# 16ChFNIRS.net
KiCad netlist of a schematic drawn in EAGLE
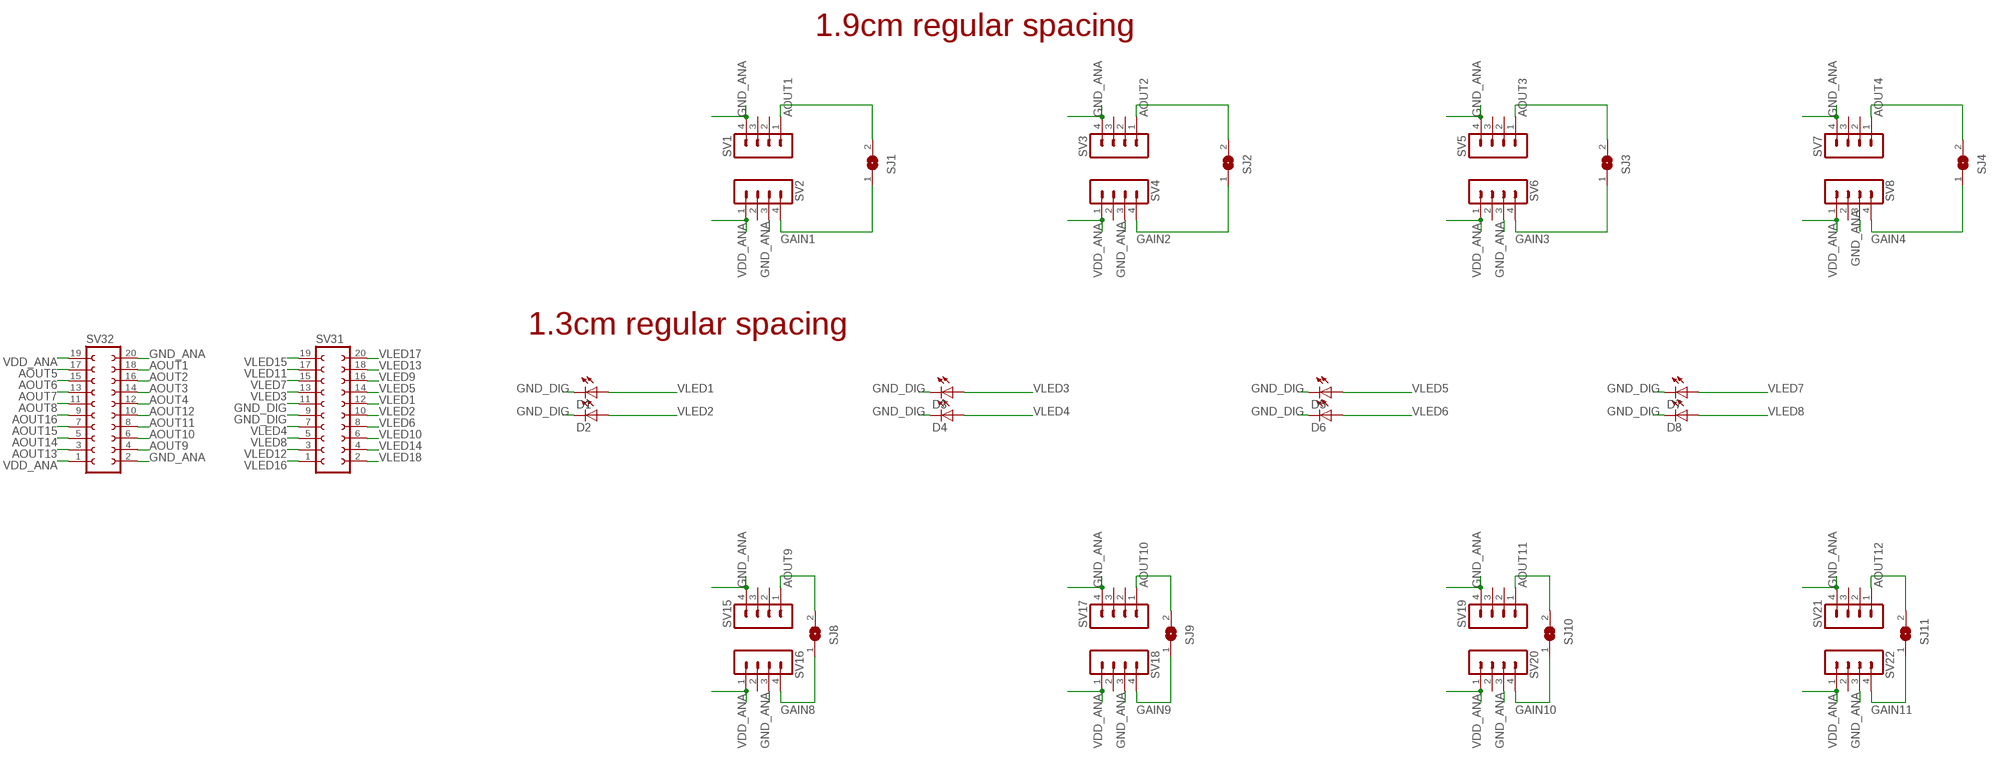
[diagram p0: schematic, sheet 1, part 1 of 2]
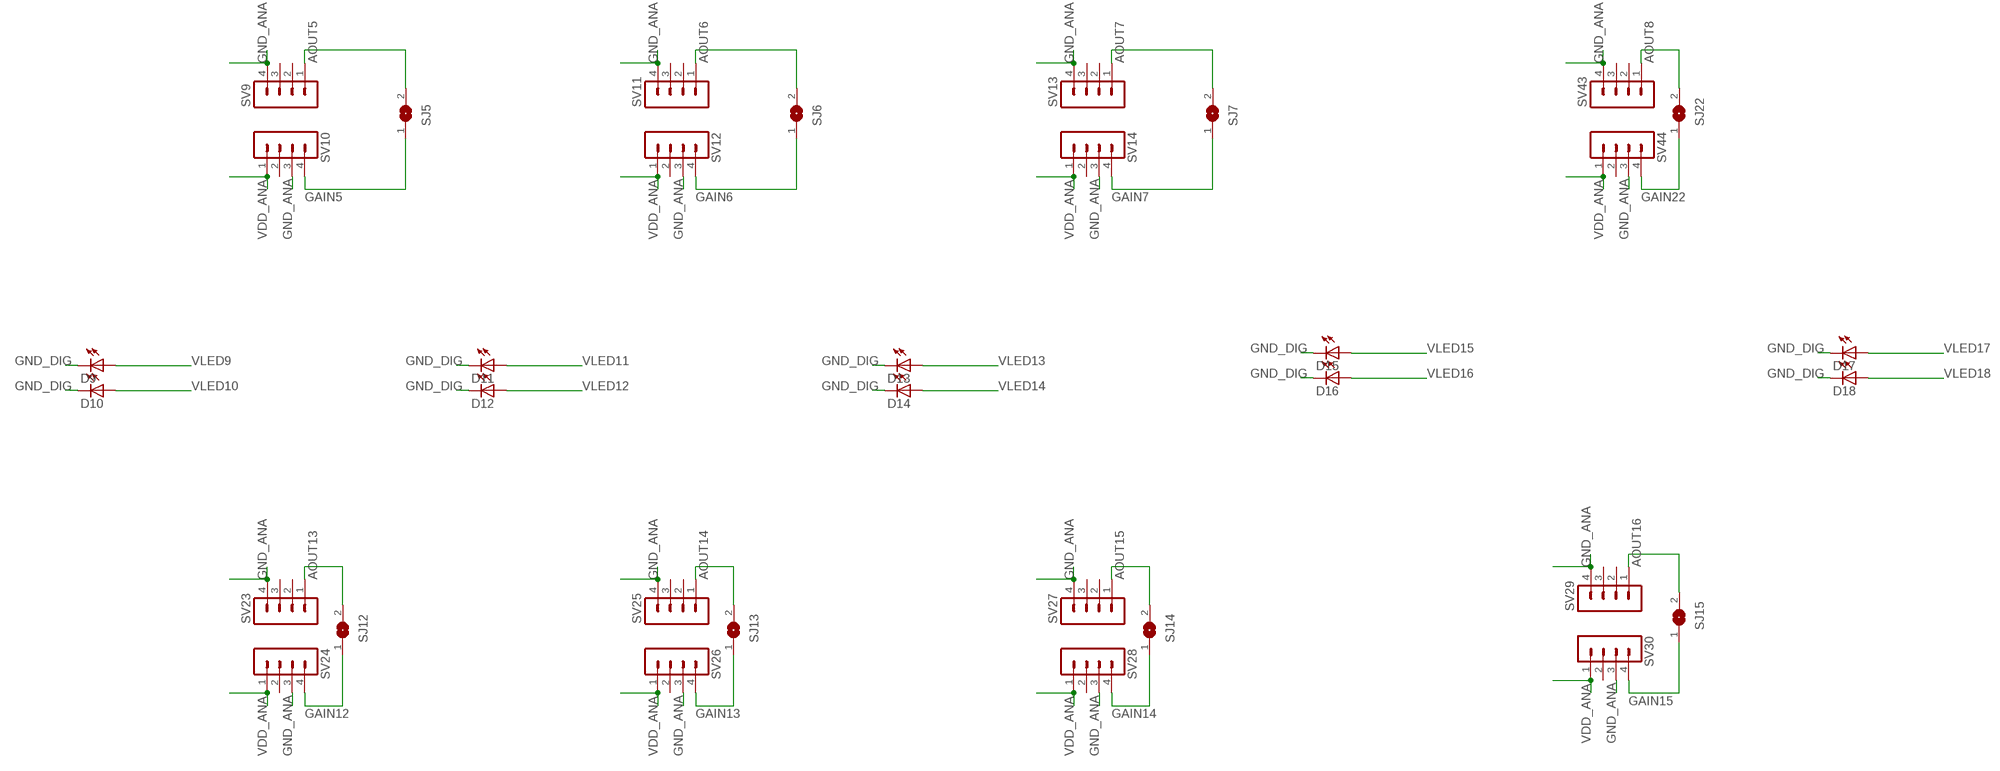
[diagram p1: schematic, sheet 1, part 2 of 2]

(export (version "E")
  (design (tool "Eeschema 10.0.6"))
  (components
    (comp (ref "D1")
      (value "LED1206")
      (footprint "eagle-import:LED-1206")
      (libsource (lib "eagle-import") (part "LED1206"))
    )
    (comp (ref "D2")
      (value "LED1206")
      (footprint "eagle-import:LED-1206")
      (libsource (lib "eagle-import") (part "LED1206"))
    )
    (comp (ref "D3")
      (value "LED1206")
      (footprint "eagle-import:LED-1206")
      (libsource (lib "eagle-import") (part "LED1206"))
    )
    (comp (ref "D4")
      (value "LED1206")
      (footprint "eagle-import:LED-1206")
      (libsource (lib "eagle-import") (part "LED1206"))
    )
    (comp (ref "D5")
      (value "LED1206")
      (footprint "eagle-import:LED-1206")
      (libsource (lib "eagle-import") (part "LED1206"))
    )
    (comp (ref "D6")
      (value "LED1206")
      (footprint "eagle-import:LED-1206")
      (libsource (lib "eagle-import") (part "LED1206"))
    )
    (comp (ref "D7")
      (value "LED1206")
      (footprint "eagle-import:LED-1206")
      (libsource (lib "eagle-import") (part "LED1206"))
    )
    (comp (ref "D8")
      (value "LED1206")
      (footprint "eagle-import:LED-1206")
      (libsource (lib "eagle-import") (part "LED1206"))
    )
    (comp (ref "D9")
      (value "LED1206")
      (footprint "eagle-import:LED-1206")
      (libsource (lib "eagle-import") (part "LED1206"))
    )
    (comp (ref "D10")
      (value "LED1206")
      (footprint "eagle-import:LED-1206")
      (libsource (lib "eagle-import") (part "LED1206"))
    )
    (comp (ref "D11")
      (value "LED1206")
      (footprint "eagle-import:LED-1206")
      (libsource (lib "eagle-import") (part "LED1206"))
    )
    (comp (ref "D12")
      (value "LED1206")
      (footprint "eagle-import:LED-1206")
      (libsource (lib "eagle-import") (part "LED1206"))
    )
    (comp (ref "D13")
      (value "LED1206")
      (footprint "eagle-import:LED-1206")
      (libsource (lib "eagle-import") (part "LED1206"))
    )
    (comp (ref "D14")
      (value "LED1206")
      (footprint "eagle-import:LED-1206")
      (libsource (lib "eagle-import") (part "LED1206"))
    )
    (comp (ref "D15")
      (value "LED1206")
      (footprint "eagle-import:LED-1206")
      (libsource (lib "eagle-import") (part "LED1206"))
    )
    (comp (ref "D16")
      (value "LED1206")
      (footprint "eagle-import:LED-1206")
      (libsource (lib "eagle-import") (part "LED1206"))
    )
    (comp (ref "D17")
      (value "LED1206")
      (footprint "eagle-import:LED-1206")
      (libsource (lib "eagle-import") (part "LED1206"))
    )
    (comp (ref "D18")
      (value "LED1206")
      (footprint "eagle-import:LED-1206")
      (libsource (lib "eagle-import") (part "LED1206"))
    )
    (comp (ref "SJ1") (value "SJ") (footprint "eagle-import:SJ") (libsource (lib "eagle-import") (part "SJ")))
    (comp (ref "SJ2") (value "SJ") (footprint "eagle-import:SJ") (libsource (lib "eagle-import") (part "SJ")))
    (comp (ref "SJ3") (value "SJ") (footprint "eagle-import:SJ") (libsource (lib "eagle-import") (part "SJ")))
    (comp (ref "SJ4") (value "SJ") (footprint "eagle-import:SJ") (libsource (lib "eagle-import") (part "SJ")))
    (comp (ref "SJ5") (value "SJ") (footprint "eagle-import:SJ") (libsource (lib "eagle-import") (part "SJ")))
    (comp (ref "SJ6") (value "SJ") (footprint "eagle-import:SJ") (libsource (lib "eagle-import") (part "SJ")))
    (comp (ref "SJ7") (value "SJ") (footprint "eagle-import:SJ") (libsource (lib "eagle-import") (part "SJ")))
    (comp (ref "SJ8") (value "SJ") (footprint "eagle-import:SJ") (libsource (lib "eagle-import") (part "SJ")))
    (comp (ref "SJ9") (value "SJ") (footprint "eagle-import:SJ") (libsource (lib "eagle-import") (part "SJ")))
    (comp (ref "SJ10")
      (value "SJ")
      (footprint "eagle-import:SJ")
      (libsource (lib "eagle-import") (part "SJ"))
    )
    (comp (ref "SJ11")
      (value "SJ")
      (footprint "eagle-import:SJ")
      (libsource (lib "eagle-import") (part "SJ"))
    )
    (comp (ref "SJ12")
      (value "SJ")
      (footprint "eagle-import:SJ")
      (libsource (lib "eagle-import") (part "SJ"))
    )
    (comp (ref "SJ13")
      (value "SJ")
      (footprint "eagle-import:SJ")
      (libsource (lib "eagle-import") (part "SJ"))
    )
    (comp (ref "SJ14")
      (value "SJ")
      (footprint "eagle-import:SJ")
      (libsource (lib "eagle-import") (part "SJ"))
    )
    (comp (ref "SJ15")
      (value "SJ")
      (footprint "eagle-import:SJ")
      (libsource (lib "eagle-import") (part "SJ"))
    )
    (comp (ref "SJ22")
      (value "SJ")
      (footprint "eagle-import:SJ")
      (libsource (lib "eagle-import") (part "SJ"))
    )
    (comp (ref "SV1")
      (value "MA04-1")
      (footprint "eagle-import:MA04-1")
      (libsource (lib "eagle-import") (part "MA04-1"))
    )
    (comp (ref "SV2")
      (value "MA04-1")
      (footprint "eagle-import:MA04-1")
      (libsource (lib "eagle-import") (part "MA04-1"))
    )
    (comp (ref "SV3")
      (value "MA04-1")
      (footprint "eagle-import:MA04-1")
      (libsource (lib "eagle-import") (part "MA04-1"))
    )
    (comp (ref "SV4")
      (value "MA04-1")
      (footprint "eagle-import:MA04-1")
      (libsource (lib "eagle-import") (part "MA04-1"))
    )
    (comp (ref "SV5")
      (value "MA04-1")
      (footprint "eagle-import:MA04-1")
      (libsource (lib "eagle-import") (part "MA04-1"))
    )
    (comp (ref "SV6")
      (value "MA04-1")
      (footprint "eagle-import:MA04-1")
      (libsource (lib "eagle-import") (part "MA04-1"))
    )
    (comp (ref "SV7")
      (value "MA04-1")
      (footprint "eagle-import:MA04-1")
      (libsource (lib "eagle-import") (part "MA04-1"))
    )
    (comp (ref "SV8")
      (value "MA04-1")
      (footprint "eagle-import:MA04-1")
      (libsource (lib "eagle-import") (part "MA04-1"))
    )
    (comp (ref "SV9")
      (value "MA04-1")
      (footprint "eagle-import:MA04-1")
      (libsource (lib "eagle-import") (part "MA04-1"))
    )
    (comp (ref "SV10")
      (value "MA04-1")
      (footprint "eagle-import:MA04-1")
      (libsource (lib "eagle-import") (part "MA04-1"))
    )
    (comp (ref "SV11")
      (value "MA04-1")
      (footprint "eagle-import:MA04-1")
      (libsource (lib "eagle-import") (part "MA04-1"))
    )
    (comp (ref "SV12")
      (value "MA04-1")
      (footprint "eagle-import:MA04-1")
      (libsource (lib "eagle-import") (part "MA04-1"))
    )
    (comp (ref "SV13")
      (value "MA04-1")
      (footprint "eagle-import:MA04-1")
      (libsource (lib "eagle-import") (part "MA04-1"))
    )
    (comp (ref "SV14")
      (value "MA04-1")
      (footprint "eagle-import:MA04-1")
      (libsource (lib "eagle-import") (part "MA04-1"))
    )
    (comp (ref "SV15")
      (value "MA04-1")
      (footprint "eagle-import:MA04-1")
      (libsource (lib "eagle-import") (part "MA04-1"))
    )
    (comp (ref "SV16")
      (value "MA04-1")
      (footprint "eagle-import:MA04-1")
      (libsource (lib "eagle-import") (part "MA04-1"))
    )
    (comp (ref "SV17")
      (value "MA04-1")
      (footprint "eagle-import:MA04-1")
      (libsource (lib "eagle-import") (part "MA04-1"))
    )
    (comp (ref "SV18")
      (value "MA04-1")
      (footprint "eagle-import:MA04-1")
      (libsource (lib "eagle-import") (part "MA04-1"))
    )
    (comp (ref "SV19")
      (value "MA04-1")
      (footprint "eagle-import:MA04-1")
      (libsource (lib "eagle-import") (part "MA04-1"))
    )
    (comp (ref "SV20")
      (value "MA04-1")
      (footprint "eagle-import:MA04-1")
      (libsource (lib "eagle-import") (part "MA04-1"))
    )
    (comp (ref "SV21")
      (value "MA04-1")
      (footprint "eagle-import:MA04-1")
      (libsource (lib "eagle-import") (part "MA04-1"))
    )
    (comp (ref "SV22")
      (value "MA04-1")
      (footprint "eagle-import:MA04-1")
      (libsource (lib "eagle-import") (part "MA04-1"))
    )
    (comp (ref "SV23")
      (value "MA04-1")
      (footprint "eagle-import:MA04-1")
      (libsource (lib "eagle-import") (part "MA04-1"))
    )
    (comp (ref "SV24")
      (value "MA04-1")
      (footprint "eagle-import:MA04-1")
      (libsource (lib "eagle-import") (part "MA04-1"))
    )
    (comp (ref "SV25")
      (value "MA04-1")
      (footprint "eagle-import:MA04-1")
      (libsource (lib "eagle-import") (part "MA04-1"))
    )
    (comp (ref "SV26")
      (value "MA04-1")
      (footprint "eagle-import:MA04-1")
      (libsource (lib "eagle-import") (part "MA04-1"))
    )
    (comp (ref "SV27")
      (value "MA04-1")
      (footprint "eagle-import:MA04-1")
      (libsource (lib "eagle-import") (part "MA04-1"))
    )
    (comp (ref "SV28")
      (value "MA04-1")
      (footprint "eagle-import:MA04-1")
      (libsource (lib "eagle-import") (part "MA04-1"))
    )
    (comp (ref "SV29")
      (value "MA04-1")
      (footprint "eagle-import:MA04-1")
      (libsource (lib "eagle-import") (part "MA04-1"))
    )
    (comp (ref "SV30")
      (value "MA04-1")
      (footprint "eagle-import:MA04-1")
      (libsource (lib "eagle-import") (part "MA04-1"))
    )
    (comp (ref "SV31")
      (value "FE10-2")
      (footprint "eagle-import:FE10-2")
      (libsource (lib "eagle-import") (part "FE10-2"))
    )
    (comp (ref "SV32")
      (value "FE10-2")
      (footprint "eagle-import:FE10-2")
      (libsource (lib "eagle-import") (part "FE10-2"))
    )
    (comp (ref "SV43")
      (value "MA04-1")
      (footprint "eagle-import:MA04-1")
      (libsource (lib "eagle-import") (part "MA04-1"))
    )
    (comp (ref "SV44")
      (value "MA04-1")
      (footprint "eagle-import:MA04-1")
      (libsource (lib "eagle-import") (part "MA04-1"))
    )
  )
  (nets
    (net (code "1") (name "/AOUT1") (class "Default")
      (node (ref "SJ1") (pin "2") (pinfunction "2_2") (pintype "passive"))
      (node (ref "SV1") (pin "1") (pinfunction "1_1") (pintype "passive"))
      (node (ref "SV32") (pin "18") (pinfunction "18_18") (pintype "passive"))
    )
    (net (code "2") (name "/AOUT2") (class "Default")
      (node (ref "SJ2") (pin "2") (pinfunction "2_2") (pintype "passive"))
      (node (ref "SV3") (pin "1") (pinfunction "1_1") (pintype "passive"))
      (node (ref "SV32") (pin "16") (pinfunction "16_16") (pintype "passive"))
    )
    (net (code "3") (name "/AOUT3") (class "Default")
      (node (ref "SJ3") (pin "2") (pinfunction "2_2") (pintype "passive"))
      (node (ref "SV32") (pin "14") (pinfunction "14_14") (pintype "passive"))
      (node (ref "SV5") (pin "1") (pinfunction "1_1") (pintype "passive"))
    )
    (net (code "4") (name "/AOUT4") (class "Default")
      (node (ref "SJ4") (pin "2") (pinfunction "2_2") (pintype "passive"))
      (node (ref "SV32") (pin "12") (pinfunction "12_12") (pintype "passive"))
      (node (ref "SV7") (pin "1") (pinfunction "1_1") (pintype "passive"))
    )
    (net (code "5") (name "/AOUT5") (class "Default")
      (node (ref "SJ5") (pin "2") (pinfunction "2_2") (pintype "passive"))
      (node (ref "SV32") (pin "17") (pinfunction "17_17") (pintype "passive"))
      (node (ref "SV9") (pin "1") (pinfunction "1_1") (pintype "passive"))
    )
    (net (code "6") (name "/AOUT6") (class "Default")
      (node (ref "SJ6") (pin "2") (pinfunction "2_2") (pintype "passive"))
      (node (ref "SV11") (pin "1") (pinfunction "1_1") (pintype "passive"))
      (node (ref "SV32") (pin "15") (pinfunction "15_15") (pintype "passive"))
    )
    (net (code "7") (name "/AOUT7") (class "Default")
      (node (ref "SJ7") (pin "2") (pinfunction "2_2") (pintype "passive"))
      (node (ref "SV13") (pin "1") (pinfunction "1_1") (pintype "passive"))
      (node (ref "SV32") (pin "13") (pinfunction "13_13") (pintype "passive"))
    )
    (net (code "8") (name "/AOUT8") (class "Default")
      (node (ref "SJ22") (pin "2") (pinfunction "2_2") (pintype "passive"))
      (node (ref "SV32") (pin "11") (pinfunction "11_11") (pintype "passive"))
      (node (ref "SV43") (pin "1") (pinfunction "1_1") (pintype "passive"))
    )
    (net (code "9") (name "/AOUT9") (class "Default")
      (node (ref "SJ8") (pin "2") (pinfunction "2_2") (pintype "passive"))
      (node (ref "SV15") (pin "1") (pinfunction "1_1") (pintype "passive"))
      (node (ref "SV32") (pin "4") (pinfunction "4_4") (pintype "passive"))
    )
    (net (code "10") (name "/AOUT10") (class "Default")
      (node (ref "SJ9") (pin "2") (pinfunction "2_2") (pintype "passive"))
      (node (ref "SV17") (pin "1") (pinfunction "1_1") (pintype "passive"))
      (node (ref "SV32") (pin "6") (pinfunction "6_6") (pintype "passive"))
    )
    (net (code "11") (name "/AOUT11") (class "Default")
      (node (ref "SJ10") (pin "2") (pinfunction "2_2") (pintype "passive"))
      (node (ref "SV19") (pin "1") (pinfunction "1_1") (pintype "passive"))
      (node (ref "SV32") (pin "8") (pinfunction "8_8") (pintype "passive"))
    )
    (net (code "12") (name "/AOUT12") (class "Default")
      (node (ref "SJ11") (pin "2") (pinfunction "2_2") (pintype "passive"))
      (node (ref "SV21") (pin "1") (pinfunction "1_1") (pintype "passive"))
      (node (ref "SV32") (pin "10") (pinfunction "10_10") (pintype "passive"))
    )
    (net (code "13") (name "/AOUT13") (class "Default")
      (node (ref "SJ12") (pin "2") (pinfunction "2_2") (pintype "passive"))
      (node (ref "SV23") (pin "1") (pinfunction "1_1") (pintype "passive"))
      (node (ref "SV32") (pin "3") (pinfunction "3_3") (pintype "passive"))
    )
    (net (code "14") (name "/AOUT14") (class "Default")
      (node (ref "SJ13") (pin "2") (pinfunction "2_2") (pintype "passive"))
      (node (ref "SV25") (pin "1") (pinfunction "1_1") (pintype "passive"))
      (node (ref "SV32") (pin "5") (pinfunction "5_5") (pintype "passive"))
    )
    (net (code "15") (name "/AOUT15") (class "Default")
      (node (ref "SJ14") (pin "2") (pinfunction "2_2") (pintype "passive"))
      (node (ref "SV27") (pin "1") (pinfunction "1_1") (pintype "passive"))
      (node (ref "SV32") (pin "7") (pinfunction "7_7") (pintype "passive"))
    )
    (net (code "16") (name "/AOUT16") (class "Default")
      (node (ref "SJ15") (pin "2") (pinfunction "2_2") (pintype "passive"))
      (node (ref "SV29") (pin "1") (pinfunction "1_1") (pintype "passive"))
      (node (ref "SV32") (pin "9") (pinfunction "9_9") (pintype "passive"))
    )
    (net (code "17") (name "/GAIN1") (class "Default")
      (node (ref "SJ1") (pin "1") (pinfunction "1_1") (pintype "passive"))
      (node (ref "SV2") (pin "4") (pinfunction "4_4") (pintype "passive"))
    )
    (net (code "18") (name "/GAIN2") (class "Default")
      (node (ref "SJ2") (pin "1") (pinfunction "1_1") (pintype "passive"))
      (node (ref "SV4") (pin "4") (pinfunction "4_4") (pintype "passive"))
    )
    (net (code "19") (name "/GAIN3") (class "Default")
      (node (ref "SJ3") (pin "1") (pinfunction "1_1") (pintype "passive"))
      (node (ref "SV6") (pin "4") (pinfunction "4_4") (pintype "passive"))
    )
    (net (code "20") (name "/GAIN4") (class "Default")
      (node (ref "SJ4") (pin "1") (pinfunction "1_1") (pintype "passive"))
      (node (ref "SV8") (pin "4") (pinfunction "4_4") (pintype "passive"))
    )
    (net (code "21") (name "/GAIN5") (class "Default")
      (node (ref "SJ5") (pin "1") (pinfunction "1_1") (pintype "passive"))
      (node (ref "SV10") (pin "4") (pinfunction "4_4") (pintype "passive"))
    )
    (net (code "22") (name "/GAIN6") (class "Default")
      (node (ref "SJ6") (pin "1") (pinfunction "1_1") (pintype "passive"))
      (node (ref "SV12") (pin "4") (pinfunction "4_4") (pintype "passive"))
    )
    (net (code "23") (name "/GAIN7") (class "Default")
      (node (ref "SJ7") (pin "1") (pinfunction "1_1") (pintype "passive"))
      (node (ref "SV14") (pin "4") (pinfunction "4_4") (pintype "passive"))
    )
    (net (code "24") (name "/GAIN8") (class "Default")
      (node (ref "SJ8") (pin "1") (pinfunction "1_1") (pintype "passive"))
      (node (ref "SV16") (pin "4") (pinfunction "4_4") (pintype "passive"))
    )
    (net (code "25") (name "/GAIN9") (class "Default")
      (node (ref "SJ9") (pin "1") (pinfunction "1_1") (pintype "passive"))
      (node (ref "SV18") (pin "4") (pinfunction "4_4") (pintype "passive"))
    )
    (net (code "26") (name "/GAIN10") (class "Default")
      (node (ref "SJ10") (pin "1") (pinfunction "1_1") (pintype "passive"))
      (node (ref "SV20") (pin "4") (pinfunction "4_4") (pintype "passive"))
    )
    (net (code "27") (name "/GAIN11") (class "Default")
      (node (ref "SJ11") (pin "1") (pinfunction "1_1") (pintype "passive"))
      (node (ref "SV22") (pin "4") (pinfunction "4_4") (pintype "passive"))
    )
    (net (code "28") (name "/GAIN12") (class "Default")
      (node (ref "SJ12") (pin "1") (pinfunction "1_1") (pintype "passive"))
      (node (ref "SV24") (pin "4") (pinfunction "4_4") (pintype "passive"))
    )
    (net (code "29") (name "/GAIN13") (class "Default")
      (node (ref "SJ13") (pin "1") (pinfunction "1_1") (pintype "passive"))
      (node (ref "SV26") (pin "4") (pinfunction "4_4") (pintype "passive"))
    )
    (net (code "30") (name "/GAIN14") (class "Default")
      (node (ref "SJ14") (pin "1") (pinfunction "1_1") (pintype "passive"))
      (node (ref "SV28") (pin "4") (pinfunction "4_4") (pintype "passive"))
    )
    (net (code "31") (name "/GAIN15") (class "Default")
      (node (ref "SJ15") (pin "1") (pinfunction "1_1") (pintype "passive"))
      (node (ref "SV30") (pin "4") (pinfunction "4_4") (pintype "passive"))
    )
    (net (code "32") (name "/GAIN22") (class "Default")
      (node (ref "SJ22") (pin "1") (pinfunction "1_1") (pintype "passive"))
      (node (ref "SV44") (pin "4") (pinfunction "4_4") (pintype "passive"))
    )
    (net (code "33") (name "/GND_ANA") (class "Default")
      (node (ref "SV1") (pin "4") (pinfunction "4_4") (pintype "passive"))
      (node (ref "SV10") (pin "3") (pinfunction "3_3") (pintype "passive"))
      (node (ref "SV11") (pin "4") (pinfunction "4_4") (pintype "passive"))
      (node (ref "SV12") (pin "3") (pinfunction "3_3") (pintype "passive"))
      (node (ref "SV13") (pin "4") (pinfunction "4_4") (pintype "passive"))
      (node (ref "SV14") (pin "3") (pinfunction "3_3") (pintype "passive"))
      (node (ref "SV15") (pin "4") (pinfunction "4_4") (pintype "passive"))
      (node (ref "SV16") (pin "3") (pinfunction "3_3") (pintype "passive"))
      (node (ref "SV17") (pin "4") (pinfunction "4_4") (pintype "passive"))
      (node (ref "SV18") (pin "3") (pinfunction "3_3") (pintype "passive"))
      (node (ref "SV19") (pin "4") (pinfunction "4_4") (pintype "passive"))
      (node (ref "SV2") (pin "3") (pinfunction "3_3") (pintype "passive"))
      (node (ref "SV20") (pin "3") (pinfunction "3_3") (pintype "passive"))
      (node (ref "SV21") (pin "4") (pinfunction "4_4") (pintype "passive"))
      (node (ref "SV22") (pin "3") (pinfunction "3_3") (pintype "passive"))
      (node (ref "SV23") (pin "4") (pinfunction "4_4") (pintype "passive"))
      (node (ref "SV24") (pin "3") (pinfunction "3_3") (pintype "passive"))
      (node (ref "SV25") (pin "4") (pinfunction "4_4") (pintype "passive"))
      (node (ref "SV26") (pin "3") (pinfunction "3_3") (pintype "passive"))
      (node (ref "SV27") (pin "4") (pinfunction "4_4") (pintype "passive"))
      (node (ref "SV28") (pin "3") (pinfunction "3_3") (pintype "passive"))
      (node (ref "SV29") (pin "4") (pinfunction "4_4") (pintype "passive"))
      (node (ref "SV3") (pin "4") (pinfunction "4_4") (pintype "passive"))
      (node (ref "SV30") (pin "3") (pinfunction "3_3") (pintype "passive"))
      (node (ref "SV32") (pin "2") (pinfunction "2_2") (pintype "passive"))
      (node (ref "SV32") (pin "20") (pinfunction "20_20") (pintype "passive"))
      (node (ref "SV4") (pin "3") (pinfunction "3_3") (pintype "passive"))
      (node (ref "SV43") (pin "4") (pinfunction "4_4") (pintype "passive"))
      (node (ref "SV44") (pin "3") (pinfunction "3_3") (pintype "passive"))
      (node (ref "SV5") (pin "4") (pinfunction "4_4") (pintype "passive"))
      (node (ref "SV6") (pin "3") (pinfunction "3_3") (pintype "passive"))
      (node (ref "SV7") (pin "4") (pinfunction "4_4") (pintype "passive"))
      (node (ref "SV8") (pin "3") (pinfunction "3_3") (pintype "passive"))
      (node (ref "SV9") (pin "4") (pinfunction "4_4") (pintype "passive"))
    )
    (net (code "34") (name "/GND_DIG") (class "Default")
      (node (ref "D1") (pin "C") (pinfunction "C_C") (pintype "passive"))
      (node (ref "D10") (pin "C") (pinfunction "C_C") (pintype "passive"))
      (node (ref "D11") (pin "C") (pinfunction "C_C") (pintype "passive"))
      (node (ref "D12") (pin "C") (pinfunction "C_C") (pintype "passive"))
      (node (ref "D13") (pin "C") (pinfunction "C_C") (pintype "passive"))
      (node (ref "D14") (pin "C") (pinfunction "C_C") (pintype "passive"))
      (node (ref "D15") (pin "C") (pinfunction "C_C") (pintype "passive"))
      (node (ref "D16") (pin "C") (pinfunction "C_C") (pintype "passive"))
      (node (ref "D17") (pin "C") (pinfunction "C_C") (pintype "passive"))
      (node (ref "D18") (pin "C") (pinfunction "C_C") (pintype "passive"))
      (node (ref "D2") (pin "C") (pinfunction "C_C") (pintype "passive"))
      (node (ref "D3") (pin "C") (pinfunction "C_C") (pintype "passive"))
      (node (ref "D4") (pin "C") (pinfunction "C_C") (pintype "passive"))
      (node (ref "D5") (pin "C") (pinfunction "C_C") (pintype "passive"))
      (node (ref "D6") (pin "C") (pinfunction "C_C") (pintype "passive"))
      (node (ref "D7") (pin "C") (pinfunction "C_C") (pintype "passive"))
      (node (ref "D8") (pin "C") (pinfunction "C_C") (pintype "passive"))
      (node (ref "D9") (pin "C") (pinfunction "C_C") (pintype "passive"))
      (node (ref "SV31") (pin "11") (pinfunction "11_11") (pintype "passive"))
      (node (ref "SV31") (pin "9") (pinfunction "9_9") (pintype "passive"))
    )
    (net (code "35") (name "/VDD_ANA") (class "Default")
      (node (ref "SV10") (pin "1") (pinfunction "1_1") (pintype "passive"))
      (node (ref "SV12") (pin "1") (pinfunction "1_1") (pintype "passive"))
      (node (ref "SV14") (pin "1") (pinfunction "1_1") (pintype "passive"))
      (node (ref "SV16") (pin "1") (pinfunction "1_1") (pintype "passive"))
      (node (ref "SV18") (pin "1") (pinfunction "1_1") (pintype "passive"))
      (node (ref "SV2") (pin "1") (pinfunction "1_1") (pintype "passive"))
      (node (ref "SV20") (pin "1") (pinfunction "1_1") (pintype "passive"))
      (node (ref "SV22") (pin "1") (pinfunction "1_1") (pintype "passive"))
      (node (ref "SV24") (pin "1") (pinfunction "1_1") (pintype "passive"))
      (node (ref "SV26") (pin "1") (pinfunction "1_1") (pintype "passive"))
      (node (ref "SV28") (pin "1") (pinfunction "1_1") (pintype "passive"))
      (node (ref "SV30") (pin "1") (pinfunction "1_1") (pintype "passive"))
      (node (ref "SV32") (pin "1") (pinfunction "1_1") (pintype "passive"))
      (node (ref "SV32") (pin "19") (pinfunction "19_19") (pintype "passive"))
      (node (ref "SV4") (pin "1") (pinfunction "1_1") (pintype "passive"))
      (node (ref "SV44") (pin "1") (pinfunction "1_1") (pintype "passive"))
      (node (ref "SV6") (pin "1") (pinfunction "1_1") (pintype "passive"))
      (node (ref "SV8") (pin "1") (pinfunction "1_1") (pintype "passive"))
    )
    (net (code "36") (name "/VLED1") (class "Default")
      (node (ref "D1") (pin "A") (pinfunction "A_A") (pintype "passive"))
      (node (ref "SV31") (pin "12") (pinfunction "12_12") (pintype "passive"))
    )
    (net (code "37") (name "/VLED2") (class "Default")
      (node (ref "D2") (pin "A") (pinfunction "A_A") (pintype "passive"))
      (node (ref "SV31") (pin "10") (pinfunction "10_10") (pintype "passive"))
    )
    (net (code "38") (name "/VLED3") (class "Default")
      (node (ref "D3") (pin "A") (pinfunction "A_A") (pintype "passive"))
      (node (ref "SV31") (pin "13") (pinfunction "13_13") (pintype "passive"))
    )
    (net (code "39") (name "/VLED4") (class "Default")
      (node (ref "D4") (pin "A") (pinfunction "A_A") (pintype "passive"))
      (node (ref "SV31") (pin "7") (pinfunction "7_7") (pintype "passive"))
    )
    (net (code "40") (name "/VLED5") (class "Default")
      (node (ref "D5") (pin "A") (pinfunction "A_A") (pintype "passive"))
      (node (ref "SV31") (pin "14") (pinfunction "14_14") (pintype "passive"))
    )
    (net (code "41") (name "/VLED6") (class "Default")
      (node (ref "D6") (pin "A") (pinfunction "A_A") (pintype "passive"))
      (node (ref "SV31") (pin "8") (pinfunction "8_8") (pintype "passive"))
    )
    (net (code "42") (name "/VLED7") (class "Default")
      (node (ref "D7") (pin "A") (pinfunction "A_A") (pintype "passive"))
      (node (ref "SV31") (pin "15") (pinfunction "15_15") (pintype "passive"))
    )
    (net (code "43") (name "/VLED8") (class "Default")
      (node (ref "D8") (pin "A") (pinfunction "A_A") (pintype "passive"))
      (node (ref "SV31") (pin "5") (pinfunction "5_5") (pintype "passive"))
    )
    (net (code "44") (name "/VLED9") (class "Default")
      (node (ref "D9") (pin "A") (pinfunction "A_A") (pintype "passive"))
      (node (ref "SV31") (pin "16") (pinfunction "16_16") (pintype "passive"))
    )
    (net (code "45") (name "/VLED10") (class "Default")
      (node (ref "D10") (pin "A") (pinfunction "A_A") (pintype "passive"))
      (node (ref "SV31") (pin "6") (pinfunction "6_6") (pintype "passive"))
    )
    (net (code "46") (name "/VLED11") (class "Default")
      (node (ref "D11") (pin "A") (pinfunction "A_A") (pintype "passive"))
      (node (ref "SV31") (pin "17") (pinfunction "17_17") (pintype "passive"))
    )
    (net (code "47") (name "/VLED12") (class "Default")
      (node (ref "D12") (pin "A") (pinfunction "A_A") (pintype "passive"))
      (node (ref "SV31") (pin "3") (pinfunction "3_3") (pintype "passive"))
    )
    (net (code "48") (name "/VLED13") (class "Default")
      (node (ref "D13") (pin "A") (pinfunction "A_A") (pintype "passive"))
      (node (ref "SV31") (pin "18") (pinfunction "18_18") (pintype "passive"))
    )
    (net (code "49") (name "/VLED14") (class "Default")
      (node (ref "D14") (pin "A") (pinfunction "A_A") (pintype "passive"))
      (node (ref "SV31") (pin "4") (pinfunction "4_4") (pintype "passive"))
    )
    (net (code "50") (name "/VLED15") (class "Default")
      (node (ref "D15") (pin "A") (pinfunction "A_A") (pintype "passive"))
      (node (ref "SV31") (pin "19") (pinfunction "19_19") (pintype "passive"))
    )
    (net (code "51") (name "/VLED16") (class "Default")
      (node (ref "D16") (pin "A") (pinfunction "A_A") (pintype "passive"))
      (node (ref "SV31") (pin "1") (pinfunction "1_1") (pintype "passive"))
    )
    (net (code "52") (name "/VLED17") (class "Default")
      (node (ref "D17") (pin "A") (pinfunction "A_A") (pintype "passive"))
      (node (ref "SV31") (pin "20") (pinfunction "20_20") (pintype "passive"))
    )
    (net (code "53") (name "/VLED18") (class "Default")
      (node (ref "D18") (pin "A") (pinfunction "A_A") (pintype "passive"))
      (node (ref "SV31") (pin "2") (pinfunction "2_2") (pintype "passive"))
    )
    (net (code "54") (name "unconnected-(SV1-Pad2)") (class "Default")
      (node (ref "SV1") (pin "2") (pinfunction "2_2") (pintype "passive"))
    )
    (net (code "55") (name "unconnected-(SV1-Pad3)") (class "Default")
      (node (ref "SV1") (pin "3") (pinfunction "3_3") (pintype "passive"))
    )
    (net (code "56") (name "unconnected-(SV2-Pad2)") (class "Default")
      (node (ref "SV2") (pin "2") (pinfunction "2_2") (pintype "passive"))
    )
    (net (code "57") (name "unconnected-(SV3-Pad2)") (class "Default")
      (node (ref "SV3") (pin "2") (pinfunction "2_2") (pintype "passive"))
    )
    (net (code "58") (name "unconnected-(SV3-Pad3)") (class "Default")
      (node (ref "SV3") (pin "3") (pinfunction "3_3") (pintype "passive"))
    )
    (net (code "59") (name "unconnected-(SV4-Pad2)") (class "Default")
      (node (ref "SV4") (pin "2") (pinfunction "2_2") (pintype "passive"))
    )
    (net (code "60") (name "unconnected-(SV5-Pad2)") (class "Default")
      (node (ref "SV5") (pin "2") (pinfunction "2_2") (pintype "passive"))
    )
    (net (code "61") (name "unconnected-(SV5-Pad3)") (class "Default")
      (node (ref "SV5") (pin "3") (pinfunction "3_3") (pintype "passive"))
    )
    (net (code "62") (name "unconnected-(SV6-Pad2)") (class "Default")
      (node (ref "SV6") (pin "2") (pinfunction "2_2") (pintype "passive"))
    )
    (net (code "63") (name "unconnected-(SV7-Pad2)") (class "Default")
      (node (ref "SV7") (pin "2") (pinfunction "2_2") (pintype "passive"))
    )
    (net (code "64") (name "unconnected-(SV7-Pad3)") (class "Default")
      (node (ref "SV7") (pin "3") (pinfunction "3_3") (pintype "passive"))
    )
    (net (code "65") (name "unconnected-(SV8-Pad2)") (class "Default")
      (node (ref "SV8") (pin "2") (pinfunction "2_2") (pintype "passive"))
    )
    (net (code "66") (name "unconnected-(SV9-Pad2)") (class "Default")
      (node (ref "SV9") (pin "2") (pinfunction "2_2") (pintype "passive"))
    )
    (net (code "67") (name "unconnected-(SV9-Pad3)") (class "Default")
      (node (ref "SV9") (pin "3") (pinfunction "3_3") (pintype "passive"))
    )
    (net (code "68") (name "unconnected-(SV10-Pad2)") (class "Default")
      (node (ref "SV10") (pin "2") (pinfunction "2_2") (pintype "passive"))
    )
    (net (code "69") (name "unconnected-(SV11-Pad2)") (class "Default")
      (node (ref "SV11") (pin "2") (pinfunction "2_2") (pintype "passive"))
    )
    (net (code "70") (name "unconnected-(SV11-Pad3)") (class "Default")
      (node (ref "SV11") (pin "3") (pinfunction "3_3") (pintype "passive"))
    )
    (net (code "71") (name "unconnected-(SV12-Pad2)") (class "Default")
      (node (ref "SV12") (pin "2") (pinfunction "2_2") (pintype "passive"))
    )
    (net (code "72") (name "unconnected-(SV13-Pad2)") (class "Default")
      (node (ref "SV13") (pin "2") (pinfunction "2_2") (pintype "passive"))
    )
    (net (code "73") (name "unconnected-(SV13-Pad3)") (class "Default")
      (node (ref "SV13") (pin "3") (pinfunction "3_3") (pintype "passive"))
    )
    (net (code "74") (name "unconnected-(SV14-Pad2)") (class "Default")
      (node (ref "SV14") (pin "2") (pinfunction "2_2") (pintype "passive"))
    )
    (net (code "75") (name "unconnected-(SV15-Pad2)") (class "Default")
      (node (ref "SV15") (pin "2") (pinfunction "2_2") (pintype "passive"))
    )
    (net (code "76") (name "unconnected-(SV15-Pad3)") (class "Default")
      (node (ref "SV15") (pin "3") (pinfunction "3_3") (pintype "passive"))
    )
    (net (code "77") (name "unconnected-(SV16-Pad2)") (class "Default")
      (node (ref "SV16") (pin "2") (pinfunction "2_2") (pintype "passive"))
    )
    (net (code "78") (name "unconnected-(SV17-Pad2)") (class "Default")
      (node (ref "SV17") (pin "2") (pinfunction "2_2") (pintype "passive"))
    )
    (net (code "79") (name "unconnected-(SV17-Pad3)") (class "Default")
      (node (ref "SV17") (pin "3") (pinfunction "3_3") (pintype "passive"))
    )
    (net (code "80") (name "unconnected-(SV18-Pad2)") (class "Default")
      (node (ref "SV18") (pin "2") (pinfunction "2_2") (pintype "passive"))
    )
    (net (code "81") (name "unconnected-(SV19-Pad2)") (class "Default")
      (node (ref "SV19") (pin "2") (pinfunction "2_2") (pintype "passive"))
    )
    (net (code "82") (name "unconnected-(SV19-Pad3)") (class "Default")
      (node (ref "SV19") (pin "3") (pinfunction "3_3") (pintype "passive"))
    )
    (net (code "83") (name "unconnected-(SV20-Pad2)") (class "Default")
      (node (ref "SV20") (pin "2") (pinfunction "2_2") (pintype "passive"))
    )
    (net (code "84") (name "unconnected-(SV21-Pad2)") (class "Default")
      (node (ref "SV21") (pin "2") (pinfunction "2_2") (pintype "passive"))
    )
    (net (code "85") (name "unconnected-(SV21-Pad3)") (class "Default")
      (node (ref "SV21") (pin "3") (pinfunction "3_3") (pintype "passive"))
    )
    (net (code "86") (name "unconnected-(SV22-Pad2)") (class "Default")
      (node (ref "SV22") (pin "2") (pinfunction "2_2") (pintype "passive"))
    )
    (net (code "87") (name "unconnected-(SV23-Pad2)") (class "Default")
      (node (ref "SV23") (pin "2") (pinfunction "2_2") (pintype "passive"))
    )
    (net (code "88") (name "unconnected-(SV23-Pad3)") (class "Default")
      (node (ref "SV23") (pin "3") (pinfunction "3_3") (pintype "passive"))
    )
    (net (code "89") (name "unconnected-(SV24-Pad2)") (class "Default")
      (node (ref "SV24") (pin "2") (pinfunction "2_2") (pintype "passive"))
    )
    (net (code "90") (name "unconnected-(SV25-Pad2)") (class "Default")
      (node (ref "SV25") (pin "2") (pinfunction "2_2") (pintype "passive"))
    )
    (net (code "91") (name "unconnected-(SV25-Pad3)") (class "Default")
      (node (ref "SV25") (pin "3") (pinfunction "3_3") (pintype "passive"))
    )
    (net (code "92") (name "unconnected-(SV26-Pad2)") (class "Default")
      (node (ref "SV26") (pin "2") (pinfunction "2_2") (pintype "passive"))
    )
    (net (code "93") (name "unconnected-(SV27-Pad2)") (class "Default")
      (node (ref "SV27") (pin "2") (pinfunction "2_2") (pintype "passive"))
    )
    (net (code "94") (name "unconnected-(SV27-Pad3)") (class "Default")
      (node (ref "SV27") (pin "3") (pinfunction "3_3") (pintype "passive"))
    )
    (net (code "95") (name "unconnected-(SV28-Pad2)") (class "Default")
      (node (ref "SV28") (pin "2") (pinfunction "2_2") (pintype "passive"))
    )
    (net (code "96") (name "unconnected-(SV29-Pad2)") (class "Default")
      (node (ref "SV29") (pin "2") (pinfunction "2_2") (pintype "passive"))
    )
    (net (code "97") (name "unconnected-(SV29-Pad3)") (class "Default")
      (node (ref "SV29") (pin "3") (pinfunction "3_3") (pintype "passive"))
    )
    (net (code "98") (name "unconnected-(SV30-Pad2)") (class "Default")
      (node (ref "SV30") (pin "2") (pinfunction "2_2") (pintype "passive"))
    )
    (net (code "99") (name "unconnected-(SV43-Pad2)") (class "Default")
      (node (ref "SV43") (pin "2") (pinfunction "2_2") (pintype "passive"))
    )
    (net (code "100") (name "unconnected-(SV43-Pad3)") (class "Default")
      (node (ref "SV43") (pin "3") (pinfunction "3_3") (pintype "passive"))
    )
    (net (code "101") (name "unconnected-(SV44-Pad2)") (class "Default")
      (node (ref "SV44") (pin "2") (pinfunction "2_2") (pintype "passive"))
    )
  )
)
